# HighCurrentSwitch.net
KiCad netlist of a schematic drawn in Altium Designer
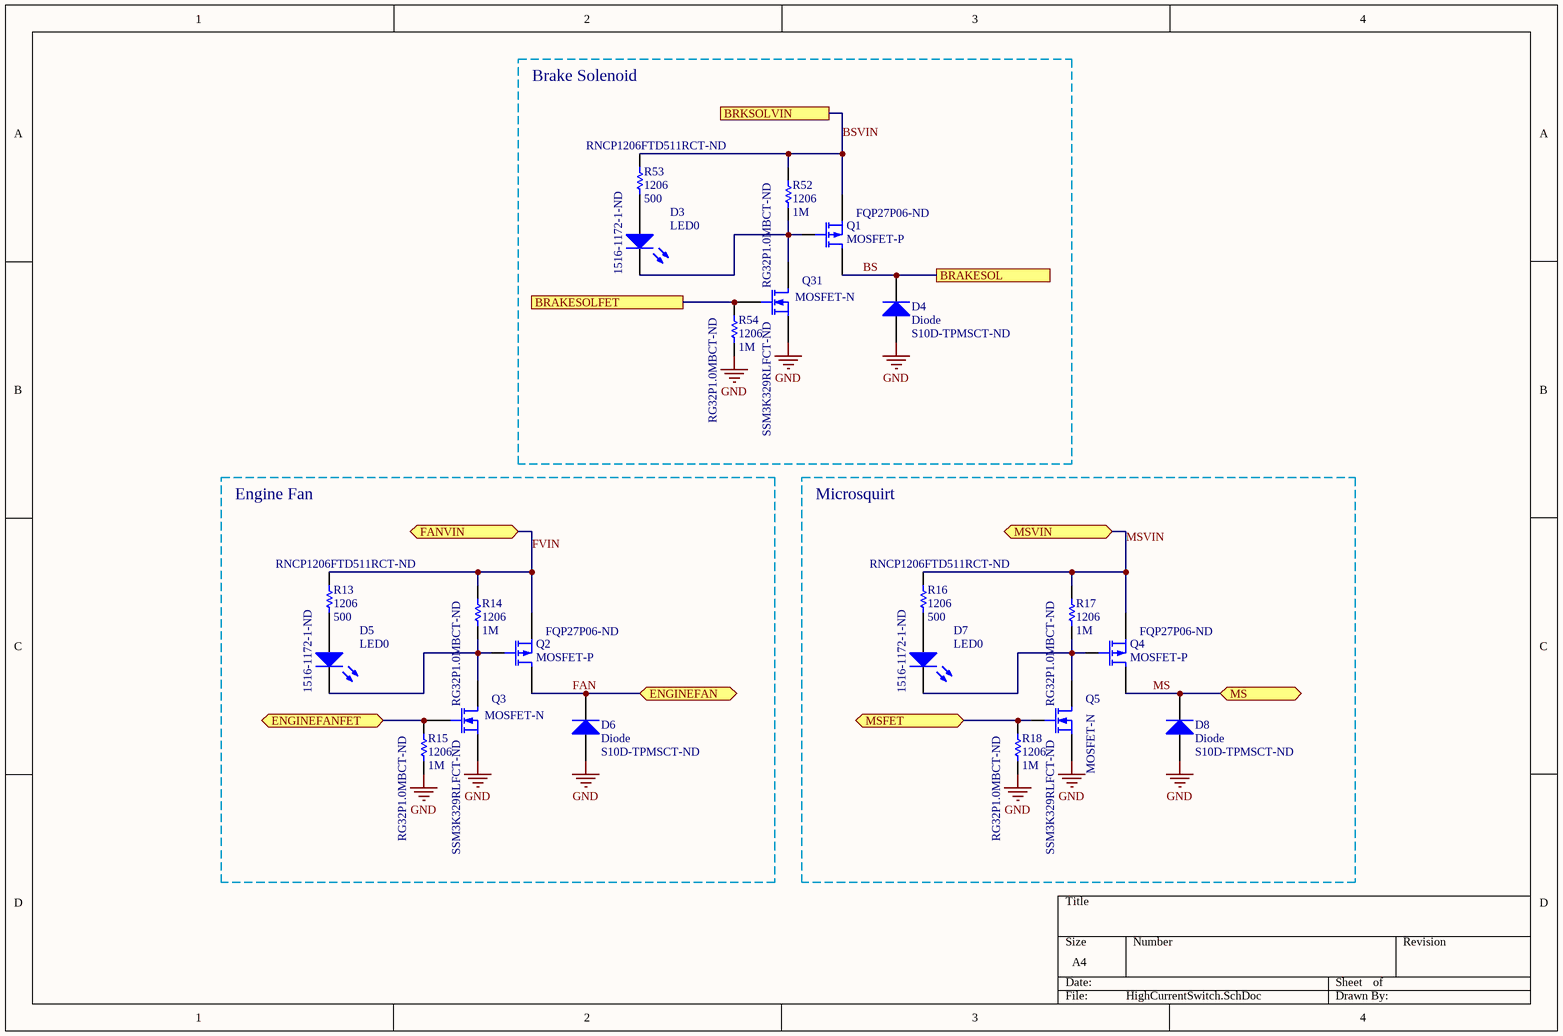
[diagram p0: HighCurrentSwitch.SchDoc]

(export (version "E")
  (design (tool "Eeschema 10.0.6"))
  (components
    (comp (ref "D3")
      (value "LED0")
      (footprint "C1206")
      (description "Typical INFRARED GaAs LED")
      (fields
        (field (name "SUPPLIER PART NUMBER 1") "1516-1172-1-ND")
        (field (name "PUBLISHER") "Altium Limited")
      )
      (libsource (lib "Miscellaneous Devices") (part "LED0"))
    )
    (comp (ref "D4")
      (value "Diode")
      (footprint "S10D-TP")
      (description "Default Diode")
      (fields
        (field (name "SUPPLIER PART NUMBER 1") "S10D-TPMSCT-ND")
        (field (name "PUBLISHER") "Altium Limited")
      )
      (libsource (lib "Miscellaneous Devices") (part "Diode"))
    )
    (comp (ref "D5")
      (value "LED0")
      (footprint "C1206")
      (description "Typical INFRARED GaAs LED")
      (fields
        (field (name "SUPPLIER PART NUMBER 1") "1516-1172-1-ND")
        (field (name "PUBLISHER") "Altium Limited")
      )
      (libsource (lib "Miscellaneous Devices") (part "LED0"))
    )
    (comp (ref "D6")
      (value "Diode")
      (footprint "S10D-TP")
      (description "Default Diode")
      (fields
        (field (name "SUPPLIER PART NUMBER 1") "S10D-TPMSCT-ND")
        (field (name "PUBLISHER") "Altium Limited")
      )
      (libsource (lib "Miscellaneous Devices") (part "Diode"))
    )
    (comp (ref "D7")
      (value "LED0")
      (footprint "C1206")
      (description "Typical INFRARED GaAs LED")
      (fields
        (field (name "SUPPLIER PART NUMBER 1") "1516-1172-1-ND")
        (field (name "PUBLISHER") "Altium Limited")
      )
      (libsource (lib "Miscellaneous Devices") (part "LED0"))
    )
    (comp (ref "D8")
      (value "Diode")
      (footprint "S10D-TP")
      (description "Default Diode")
      (fields
        (field (name "SUPPLIER PART NUMBER 1") "S10D-TPMSCT-ND")
        (field (name "PUBLISHER") "Altium Limited")
      )
      (libsource (lib "Miscellaneous Devices") (part "Diode"))
    )
    (comp (ref "Q1")
      (value "MOSFET-P")
      (footprint "TO-220")
      (description "P-Channel MOSFET")
      (fields
        (field (name "SUPPLIER PART NUMBER 1") "FQP27P06-ND")
        (field (name "PUBLISHER") "Altium Limited")
      )
      (libsource (lib "Miscellaneous Devices") (part "MOSFET-P"))
    )
    (comp (ref "Q2")
      (value "MOSFET-P")
      (footprint "TO-220")
      (description "P-Channel MOSFET")
      (fields
        (field (name "SUPPLIER PART NUMBER 1") "FQP27P06-ND")
        (field (name "PUBLISHER") "Altium Limited")
      )
      (libsource (lib "Miscellaneous Devices") (part "MOSFET-P"))
    )
    (comp (ref "Q3")
      (value "MOSFET-N")
      (footprint "SOT23f")
      (description "N-Channel MOSFET")
      (fields
        (field (name "SUPPLIER PART NUMBER 1") "SSM3K329RLFCT-ND")
        (field (name "PUBLISHER") "Altium Limited")
      )
      (libsource (lib "Miscellaneous Devices") (part "MOSFET-N"))
    )
    (comp (ref "Q4")
      (value "MOSFET-P")
      (footprint "TO-220")
      (description "P-Channel MOSFET")
      (fields
        (field (name "SUPPLIER PART NUMBER 1") "FQP27P06-ND")
        (field (name "PUBLISHER") "Altium Limited")
      )
      (libsource (lib "Miscellaneous Devices") (part "MOSFET-P"))
    )
    (comp (ref "Q5")
      (value "MOSFET-N")
      (footprint "SOT23f")
      (description "N-Channel MOSFET")
      (fields
        (field (name "SUPPLIER PART NUMBER 1") "SSM3K329RLFCT-ND")
        (field (name "PUBLISHER") "Altium Limited")
      )
      (libsource (lib "Miscellaneous Devices") (part "MOSFET-N"))
    )
    (comp (ref "Q31")
      (value "MOSFET-N")
      (footprint "SOT23f")
      (description "N-Channel MOSFET")
      (fields
        (field (name "SUPPLIER PART NUMBER 1") "SSM3K329RLFCT-ND")
        (field (name "PUBLISHER") "Altium Limited")
      )
      (libsource (lib "Miscellaneous Devices") (part "MOSFET-N"))
    )
    (comp (ref "R13")
      (value "1206")
      (footprint "C1206")
      (description "Resistor")
      (fields
        (field (name "ALTIUM_VALUE") "500")
        (field (name "SUPPLIER PART NUMBER 1") "RNCP1206FTD511RCT-ND")
        (field (name "PUBLISHER") "Altium Limited")
      )
      (libsource (lib "Miscellaneous Devices") (part "Res1"))
    )
    (comp (ref "R14")
      (value "1206")
      (footprint "1206 (High Density)")
      (description "Resistor")
      (fields
        (field (name "ALTIUM_VALUE") "1M")
        (field (name "SUPPLIER PART NUMBER 1") "RG32P1.0MBCT-ND")
        (field (name "PUBLISHER") "Altium Limited")
      )
      (libsource (lib "Miscellaneous Devices") (part "Res1"))
    )
    (comp (ref "R15")
      (value "1206")
      (footprint "1206 (High Density)")
      (description "Resistor")
      (fields
        (field (name "ALTIUM_VALUE") "1M")
        (field (name "SUPPLIER PART NUMBER 1") "RG32P1.0MBCT-ND")
        (field (name "PUBLISHER") "Altium Limited")
      )
      (libsource (lib "Miscellaneous Devices") (part "Res1"))
    )
    (comp (ref "R16")
      (value "1206")
      (footprint "C1206")
      (description "Resistor")
      (fields
        (field (name "ALTIUM_VALUE") "500")
        (field (name "SUPPLIER PART NUMBER 1") "RNCP1206FTD511RCT-ND")
        (field (name "PUBLISHER") "Altium Limited")
      )
      (libsource (lib "Miscellaneous Devices") (part "Res1"))
    )
    (comp (ref "R17")
      (value "1206")
      (footprint "1206 (High Density)")
      (description "Resistor")
      (fields
        (field (name "ALTIUM_VALUE") "1M")
        (field (name "SUPPLIER PART NUMBER 1") "RG32P1.0MBCT-ND")
        (field (name "PUBLISHER") "Altium Limited")
      )
      (libsource (lib "Miscellaneous Devices") (part "Res1"))
    )
    (comp (ref "R18")
      (value "1206")
      (footprint "1206 (High Density)")
      (description "Resistor")
      (fields
        (field (name "ALTIUM_VALUE") "1M")
        (field (name "SUPPLIER PART NUMBER 1") "RG32P1.0MBCT-ND")
        (field (name "PUBLISHER") "Altium Limited")
      )
      (libsource (lib "Miscellaneous Devices") (part "Res1"))
    )
    (comp (ref "R52")
      (value "1206")
      (footprint "1206 (High Density)")
      (description "1M Resistor")
      (fields
        (field (name "ALTIUM_VALUE") "1M")
        (field (name "SUPPLIER PART NUMBER 1") "RG32P1.0MBCT-ND")
        (field (name "PUBLISHER") "Altium Limited")
      )
      (libsource (lib "Miscellaneous Devices") (part "Res1"))
    )
    (comp (ref "R53")
      (value "1206")
      (footprint "C1206")
      (description "Resistor")
      (fields
        (field (name "ALTIUM_VALUE") "500")
        (field (name "SUPPLIER PART NUMBER 1") "RNCP1206FTD511RCT-ND")
        (field (name "PUBLISHER") "Altium Limited")
      )
      (libsource (lib "Miscellaneous Devices") (part "Res1"))
    )
    (comp (ref "R54")
      (value "1206")
      (footprint "1206 (High Density)")
      (description "Resistor")
      (fields
        (field (name "ALTIUM_VALUE") "1M")
        (field (name "SUPPLIER PART NUMBER 1") "RG32P1.0MBCT-ND")
        (field (name "PUBLISHER") "Altium Limited")
      )
      (libsource (lib "Miscellaneous Devices") (part "Res1"))
    )
  )
  (nets
    (net (code "1") (name "/BRAKESOLFET") (class "Default")
      (node (ref "Q31") (pin "2") (pinfunction "G_2") (pintype "passive"))
      (node (ref "R54") (pin "2") (pinfunction "2_2") (pintype "passive"))
    )
    (net (code "2") (name "/BS") (class "Default")
      (node (ref "D4") (pin "2") (pinfunction "K_2") (pintype "passive"))
      (node (ref "Q1") (pin "2") (pinfunction "D_2") (pintype "passive"))
    )
    (net (code "3") (name "/BSVIN") (class "Default")
      (node (ref "Q1") (pin "3") (pinfunction "S_3") (pintype "passive"))
      (node (ref "R52") (pin "2") (pinfunction "2_2") (pintype "passive"))
      (node (ref "R53") (pin "1") (pinfunction "1_1") (pintype "passive"))
    )
    (net (code "4") (name "/ENGINEFANFET") (class "Default")
      (node (ref "Q3") (pin "2") (pinfunction "G_2") (pintype "passive"))
      (node (ref "R15") (pin "2") (pinfunction "2_2") (pintype "passive"))
    )
    (net (code "5") (name "/FAN") (class "Default")
      (node (ref "D6") (pin "2") (pinfunction "K_2") (pintype "passive"))
      (node (ref "Q2") (pin "2") (pinfunction "D_2") (pintype "passive"))
    )
    (net (code "6") (name "/FVIN") (class "Default")
      (node (ref "Q2") (pin "3") (pinfunction "S_3") (pintype "passive"))
      (node (ref "R13") (pin "1") (pinfunction "1_1") (pintype "passive"))
      (node (ref "R14") (pin "2") (pinfunction "2_2") (pintype "passive"))
    )
    (net (code "7") (name "/MS") (class "Default")
      (node (ref "D8") (pin "2") (pinfunction "K_2") (pintype "passive"))
      (node (ref "Q4") (pin "2") (pinfunction "D_2") (pintype "passive"))
    )
    (net (code "8") (name "/MSFET") (class "Default")
      (node (ref "Q5") (pin "2") (pinfunction "G_2") (pintype "passive"))
      (node (ref "R18") (pin "2") (pinfunction "2_2") (pintype "passive"))
    )
    (net (code "9") (name "/MSVIN") (class "Default")
      (node (ref "Q4") (pin "3") (pinfunction "S_3") (pintype "passive"))
      (node (ref "R16") (pin "1") (pinfunction "1_1") (pintype "passive"))
      (node (ref "R17") (pin "2") (pinfunction "2_2") (pintype "passive"))
    )
    (net (code "10") (name "GND") (class "Default")
      (node (ref "D4") (pin "1") (pinfunction "A_1") (pintype "passive"))
      (node (ref "D6") (pin "1") (pinfunction "A_1") (pintype "passive"))
      (node (ref "D8") (pin "1") (pinfunction "A_1") (pintype "passive"))
      (node (ref "Q3") (pin "3") (pinfunction "S_3") (pintype "passive"))
      (node (ref "Q31") (pin "3") (pinfunction "S_3") (pintype "passive"))
      (node (ref "Q5") (pin "3") (pinfunction "S_3") (pintype "passive"))
      (node (ref "R15") (pin "1") (pinfunction "1_1") (pintype "passive"))
      (node (ref "R18") (pin "1") (pinfunction "1_1") (pintype "passive"))
      (node (ref "R54") (pin "1") (pinfunction "1_1") (pintype "passive"))
    )
    (net (code "11") (name "Net-(D3-A)") (class "Default")
      (node (ref "D3") (pin "1") (pinfunction "A_1") (pintype "passive"))
      (node (ref "R53") (pin "2") (pinfunction "2_2") (pintype "passive"))
    )
    (net (code "12") (name "Net-(D3-K)") (class "Default")
      (node (ref "D3") (pin "2") (pinfunction "K_2") (pintype "passive"))
      (node (ref "Q1") (pin "1") (pinfunction "G_1") (pintype "passive"))
      (node (ref "Q31") (pin "1") (pinfunction "D_1") (pintype "passive"))
      (node (ref "R52") (pin "1") (pinfunction "1_1") (pintype "passive"))
    )
    (net (code "13") (name "Net-(D5-A)") (class "Default")
      (node (ref "D5") (pin "1") (pinfunction "A_1") (pintype "passive"))
      (node (ref "R13") (pin "2") (pinfunction "2_2") (pintype "passive"))
    )
    (net (code "14") (name "Net-(D5-K)") (class "Default")
      (node (ref "D5") (pin "2") (pinfunction "K_2") (pintype "passive"))
      (node (ref "Q2") (pin "1") (pinfunction "G_1") (pintype "passive"))
      (node (ref "Q3") (pin "1") (pinfunction "D_1") (pintype "passive"))
      (node (ref "R14") (pin "1") (pinfunction "1_1") (pintype "passive"))
    )
    (net (code "15") (name "Net-(D7-A)") (class "Default")
      (node (ref "D7") (pin "1") (pinfunction "A_1") (pintype "passive"))
      (node (ref "R16") (pin "2") (pinfunction "2_2") (pintype "passive"))
    )
    (net (code "16") (name "Net-(D7-K)") (class "Default")
      (node (ref "D7") (pin "2") (pinfunction "K_2") (pintype "passive"))
      (node (ref "Q4") (pin "1") (pinfunction "G_1") (pintype "passive"))
      (node (ref "Q5") (pin "1") (pinfunction "D_1") (pintype "passive"))
      (node (ref "R17") (pin "1") (pinfunction "1_1") (pintype "passive"))
    )
  )
)
